# IIC_LCD.net
KiCad netlist of a schematic drawn in Altium Designer
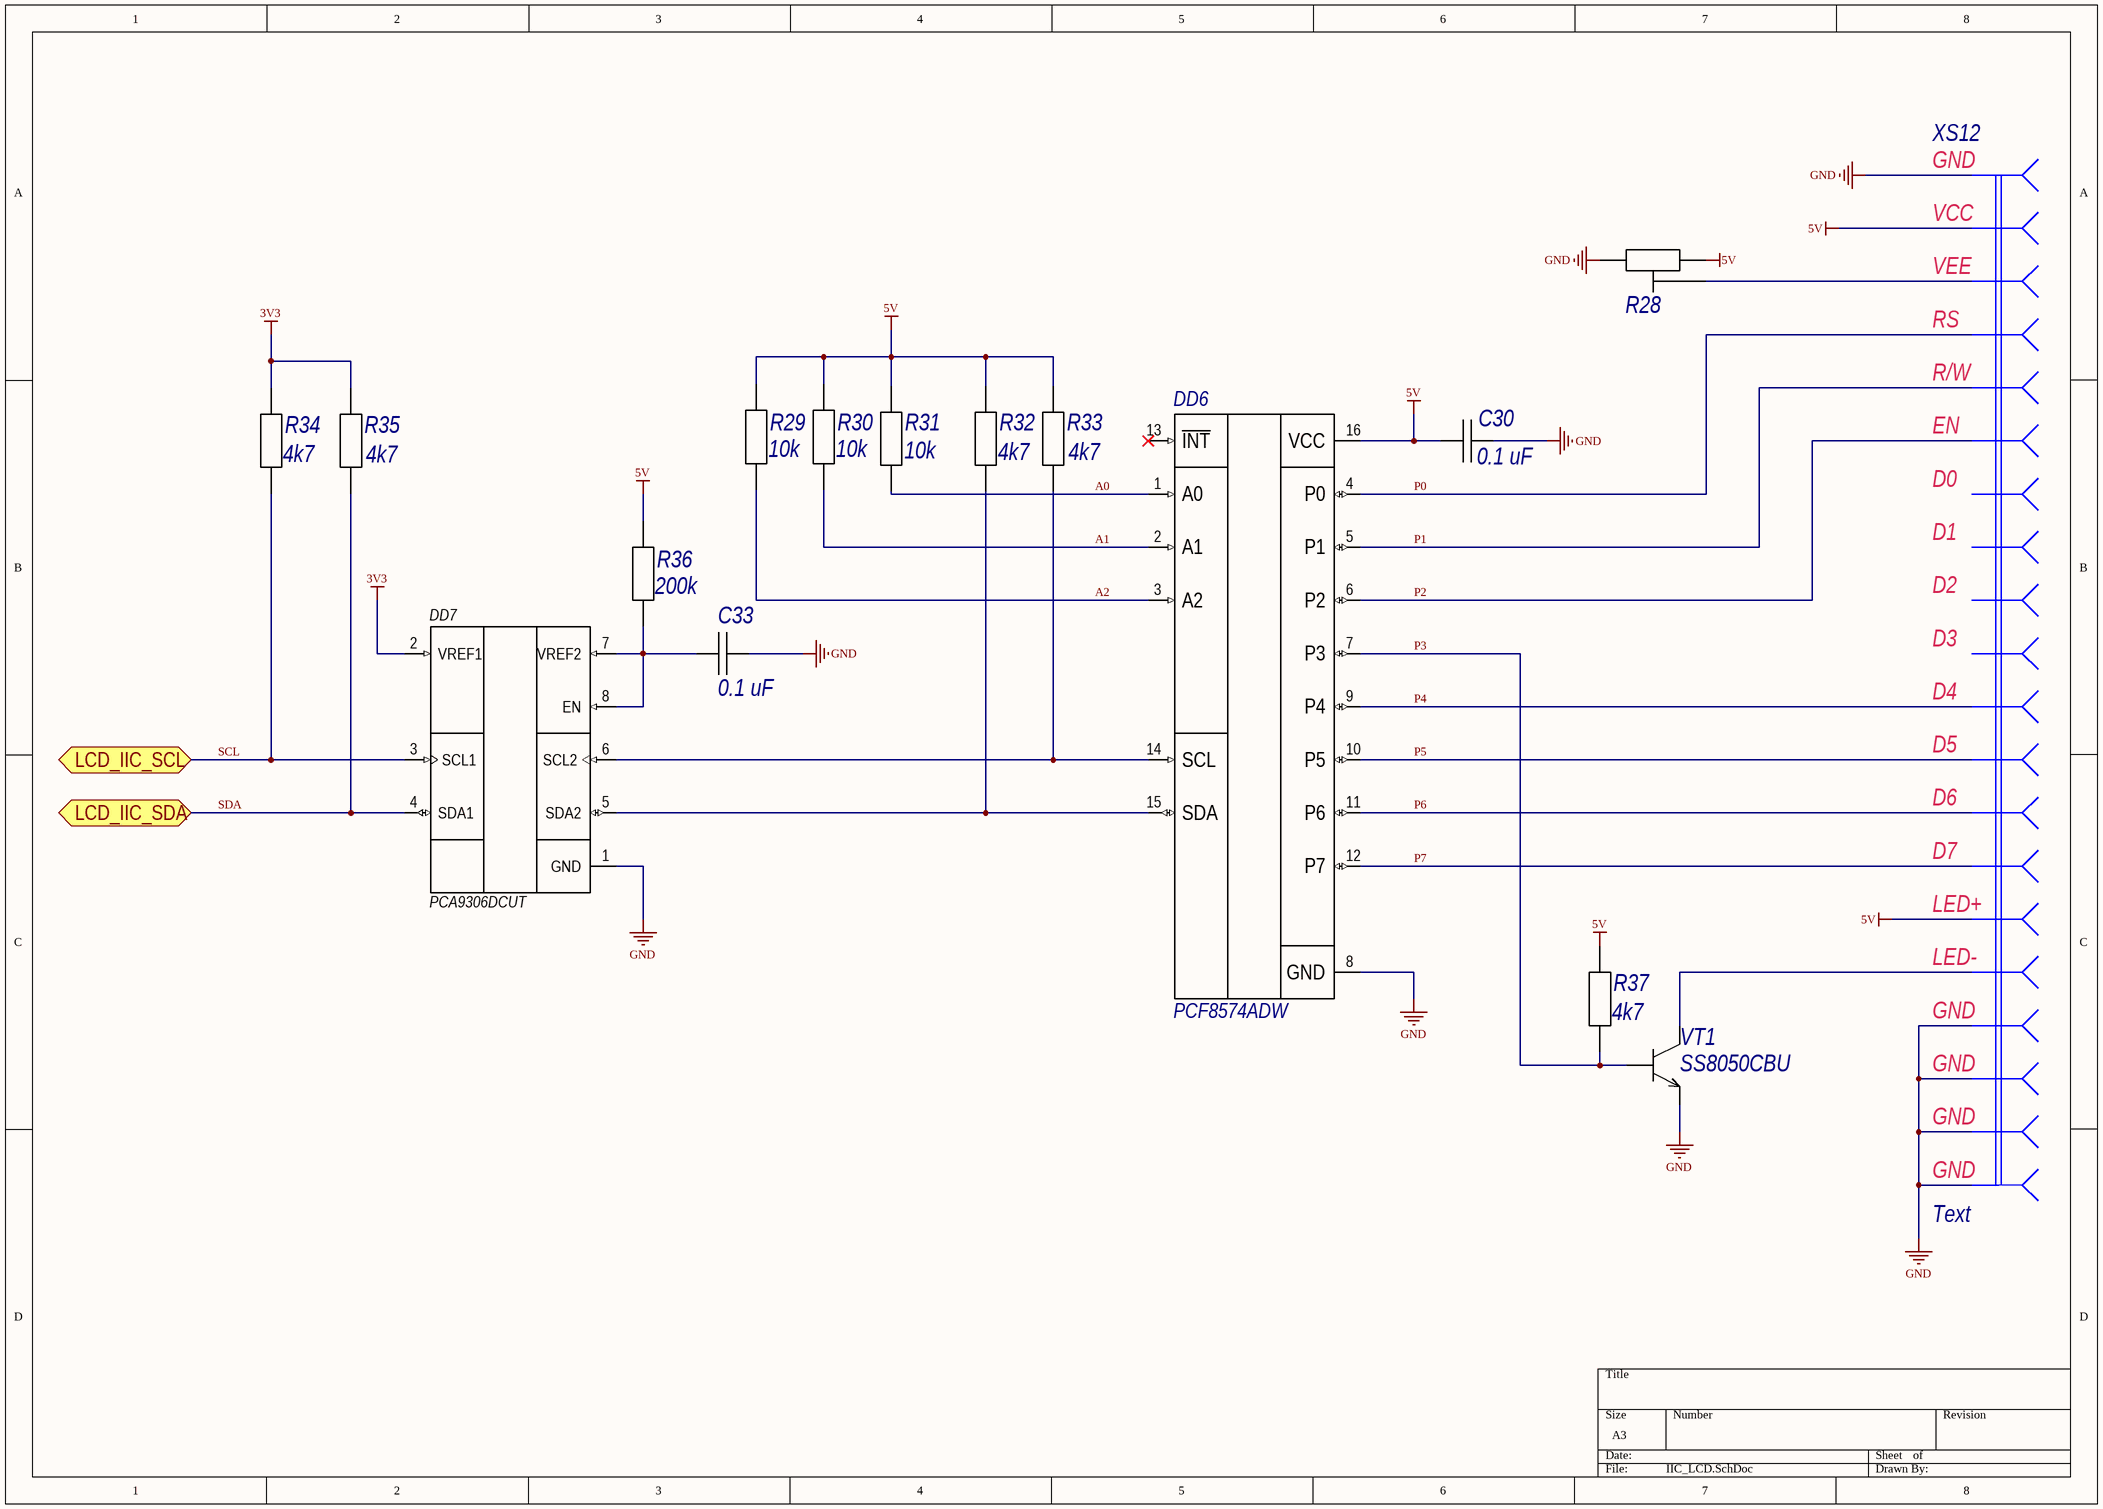
[diagram p0: IIC_LCD.SchDoc]

(export (version "E")
  (design (tool "Eeschema 10.0.6"))
  (components
    (comp (ref "C30")
      (value "0.1 uF")
      (footprint "C0805C")
      (fields (field (name "PUBLISHER") "Andrew Danich"))
      (libsource (lib "PA_control_board") (part "CAP_0805"))
    )
    (comp (ref "C33")
      (value "0.1 uF")
      (footprint "C0805C")
      (fields (field (name "PUBLISHER") "Andrew Danich"))
      (libsource (lib "PA_control_board") (part "CAP_0805"))
    )
    (comp (ref "DD6")
      (value "PCF8574ADW")
      (footprint "SOIC127P1030X265-16N")
      (description "Remote 8-Bit I/O Expander for I2C-Bus 16-SOIC -40 to 85")
      (fields (field (name "MF") "Texas Instruments"))
      (libsource (lib "PA_control_board") (part "PCF8574ADW"))
    )
    (comp (ref "DD7")
      (value "PCA9306DCUT")
      (footprint "SOP50P310X90-8N")
      (description "2-bit bidirectional I2C bus and SMBus voltage-level shifter 8-VSSOP -40 to 85")
      (fields (field (name "MF") "Texas Instruments"))
      (libsource (lib "PA_control_board") (part "PCA9306DCUT"))
    )
    (comp (ref "R28")
      (value "RES_VAR")
      (footprint "TRIM_3296W-1-254LF")
      (fields (field (name "PUBLISHER") "Andrew Danich"))
      (libsource (lib "PA_control_board") (part "RES_VAR"))
    )
    (comp (ref "R29")
      (value "10k")
      (footprint "C0805R")
      (fields (field (name "PUBLISHER") "Andrew Danich"))
      (libsource (lib "PA_control_board") (part "RES_0805"))
    )
    (comp (ref "R30")
      (value "10k")
      (footprint "C0805R")
      (fields (field (name "PUBLISHER") "Andrew Danich"))
      (libsource (lib "PA_control_board") (part "RES_0805"))
    )
    (comp (ref "R31")
      (value "10k")
      (footprint "C0805R")
      (fields (field (name "PUBLISHER") "Andrew Danich"))
      (libsource (lib "PA_control_board") (part "RES_0805"))
    )
    (comp (ref "R32")
      (value "4k7")
      (footprint "C0805R")
      (fields (field (name "PUBLISHER") "Andrew Danich"))
      (libsource (lib "PA_control_board") (part "RES_0805"))
    )
    (comp (ref "R33")
      (value "4k7")
      (footprint "C0805R")
      (fields (field (name "PUBLISHER") "Andrew Danich"))
      (libsource (lib "PA_control_board") (part "RES_0805"))
    )
    (comp (ref "R34")
      (value "4k7")
      (footprint "C0805R")
      (fields (field (name "PUBLISHER") "Andrew Danich"))
      (libsource (lib "PA_control_board") (part "RES_0805"))
    )
    (comp (ref "R35")
      (value "4k7")
      (footprint "C0805R")
      (fields (field (name "PUBLISHER") "Andrew Danich"))
      (libsource (lib "PA_control_board") (part "RES_0805"))
    )
    (comp (ref "R36")
      (value "200k")
      (footprint "C0805R")
      (fields (field (name "PUBLISHER") "Andrew Danich"))
      (libsource (lib "PA_control_board") (part "RES_0805"))
    )
    (comp (ref "R37")
      (value "4k7")
      (footprint "C0805R")
      (fields (field (name "PUBLISHER") "Andrew Danich"))
      (libsource (lib "PA_control_board") (part "RES_0805"))
    )
    (comp (ref "VT1")
      (value "SS8050CBU")
      (footprint "TO-92-A")
      (fields (field (name "PUBLISHER") "Andrew Danich"))
      (libsource (lib "PA_control_board") (part "SS8050CBU"))
    )
    (comp (ref "XS12")
      (value "Text")
      (footprint "IDC-20")
      (fields (field (name "PUBLISHER") "Andrew Danich"))
      (libsource (lib "PA_control_board") (part "CONNECT_LCD"))
    )
  )
  (nets
    (net (code "1") (name "/A0") (class "Default")
      (node (ref "DD6") (pin "1") (pinfunction "A0_1") (pintype "input"))
      (node (ref "R31") (pin "1") (pinfunction "1_1") (pintype "passive"))
    )
    (net (code "2") (name "/A1") (class "Default")
      (node (ref "DD6") (pin "2") (pinfunction "A1_2") (pintype "input"))
      (node (ref "R30") (pin "1") (pinfunction "1_1") (pintype "passive"))
    )
    (net (code "3") (name "/A2") (class "Default")
      (node (ref "DD6") (pin "3") (pinfunction "A2_3") (pintype "input"))
      (node (ref "R29") (pin "1") (pinfunction "1_1") (pintype "passive"))
    )
    (net (code "4") (name "/P0") (class "Default")
      (node (ref "DD6") (pin "4") (pinfunction "P0_4") (pintype "bidirectional"))
      (node (ref "XS12") (pin "4") (pintype "passive"))
    )
    (net (code "5") (name "/P1") (class "Default")
      (node (ref "DD6") (pin "5") (pinfunction "P1_5") (pintype "bidirectional"))
      (node (ref "XS12") (pin "5") (pintype "passive"))
    )
    (net (code "6") (name "/P2") (class "Default")
      (node (ref "DD6") (pin "6") (pinfunction "P2_6") (pintype "bidirectional"))
      (node (ref "XS12") (pin "6") (pintype "passive"))
    )
    (net (code "7") (name "/P3") (class "Default")
      (node (ref "DD6") (pin "7") (pinfunction "P3_7") (pintype "bidirectional"))
      (node (ref "R37") (pin "1") (pinfunction "1_1") (pintype "passive"))
      (node (ref "VT1") (pin "1") (pinfunction "Б_1") (pintype "passive"))
    )
    (net (code "8") (name "/P4") (class "Default")
      (node (ref "DD6") (pin "9") (pinfunction "P4_9") (pintype "bidirectional"))
      (node (ref "XS12") (pin "11") (pintype "passive"))
    )
    (net (code "9") (name "/P5") (class "Default")
      (node (ref "DD6") (pin "10") (pinfunction "P5_10") (pintype "bidirectional"))
      (node (ref "XS12") (pin "12") (pintype "passive"))
    )
    (net (code "10") (name "/P6") (class "Default")
      (node (ref "DD6") (pin "11") (pinfunction "P6_11") (pintype "bidirectional"))
      (node (ref "XS12") (pin "13") (pintype "passive"))
    )
    (net (code "11") (name "/P7") (class "Default")
      (node (ref "DD6") (pin "12") (pinfunction "P7_12") (pintype "bidirectional"))
      (node (ref "XS12") (pin "14") (pintype "passive"))
    )
    (net (code "12") (name "/SCL") (class "Default")
      (node (ref "DD7") (pin "3") (pinfunction "SCL1_3") (pintype "input"))
      (node (ref "R34") (pin "1") (pinfunction "1_1") (pintype "passive"))
    )
    (net (code "13") (name "/SDA") (class "Default")
      (node (ref "DD7") (pin "4") (pinfunction "SDA1_4") (pintype "bidirectional"))
      (node (ref "R35") (pin "1") (pinfunction "1_1") (pintype "passive"))
    )
    (net (code "14") (name "3V3") (class "Default")
      (node (ref "DD7") (pin "2") (pinfunction "VREF1_2") (pintype "input"))
      (node (ref "R34") (pin "2") (pinfunction "2_2") (pintype "passive"))
      (node (ref "R35") (pin "2") (pinfunction "2_2") (pintype "passive"))
    )
    (net (code "15") (name "5V") (class "Default")
      (node (ref "C30") (pin "2") (pinfunction "2_2") (pintype "passive"))
      (node (ref "DD6") (pin "16") (pinfunction "VCC_16") (pintype "power_in"))
      (node (ref "R28") (pin "1") (pinfunction "1_1") (pintype "passive"))
      (node (ref "R29") (pin "2") (pinfunction "2_2") (pintype "passive"))
      (node (ref "R30") (pin "2") (pinfunction "2_2") (pintype "passive"))
      (node (ref "R31") (pin "2") (pinfunction "2_2") (pintype "passive"))
      (node (ref "R32") (pin "2") (pinfunction "2_2") (pintype "passive"))
      (node (ref "R33") (pin "2") (pinfunction "2_2") (pintype "passive"))
      (node (ref "R36") (pin "2") (pinfunction "2_2") (pintype "passive"))
      (node (ref "R37") (pin "2") (pinfunction "2_2") (pintype "passive"))
      (node (ref "XS12") (pin "15") (pintype "passive"))
      (node (ref "XS12") (pin "2") (pintype "passive"))
    )
    (net (code "16") (name "GND") (class "Default")
      (node (ref "C30") (pin "1") (pinfunction "1_1") (pintype "passive"))
      (node (ref "C33") (pin "2") (pinfunction "2_2") (pintype "passive"))
      (node (ref "DD6") (pin "8") (pinfunction "GND_8") (pintype "power_in"))
      (node (ref "DD7") (pin "1") (pinfunction "GND_1") (pintype "power_in"))
      (node (ref "R28") (pin "3") (pinfunction "3_3") (pintype "passive"))
      (node (ref "VT1") (pin "3") (pinfunction "Э_3") (pintype "passive"))
      (node (ref "XS12") (pin "1") (pintype "passive"))
      (node (ref "XS12") (pin "17") (pintype "passive"))
      (node (ref "XS12") (pin "18") (pintype "passive"))
      (node (ref "XS12") (pin "19") (pintype "passive"))
      (node (ref "XS12") (pin "20") (pintype "passive"))
    )
    (net (code "17") (name "Net-(DD6-SCL)") (class "Default")
      (node (ref "DD6") (pin "14") (pinfunction "SCL_14") (pintype "input"))
      (node (ref "DD7") (pin "6") (pinfunction "SCL2_6") (pintype "input"))
      (node (ref "R33") (pin "1") (pinfunction "1_1") (pintype "passive"))
    )
    (net (code "18") (name "Net-(DD6-SDA)") (class "Default")
      (node (ref "DD6") (pin "15") (pinfunction "SDA_15") (pintype "bidirectional"))
      (node (ref "DD7") (pin "5") (pinfunction "SDA2_5") (pintype "bidirectional"))
      (node (ref "R32") (pin "1") (pinfunction "1_1") (pintype "passive"))
    )
    (net (code "19") (name "Net-(DD7-EN)") (class "Default")
      (node (ref "C33") (pin "1") (pinfunction "1_1") (pintype "passive"))
      (node (ref "DD7") (pin "7") (pinfunction "VREF2_7") (pintype "input"))
      (node (ref "DD7") (pin "8") (pinfunction "EN_8") (pintype "input"))
      (node (ref "R36") (pin "1") (pinfunction "1_1") (pintype "passive"))
    )
    (net (code "20") (name "Net-(R28-Pad2)") (class "Default")
      (node (ref "R28") (pin "2") (pinfunction "2_2") (pintype "passive"))
      (node (ref "XS12") (pin "3") (pintype "passive"))
    )
    (net (code "21") (name "Net-(VT1-К)") (class "Default")
      (node (ref "VT1") (pin "2") (pinfunction "К_2") (pintype "passive"))
      (node (ref "XS12") (pin "16") (pintype "passive"))
    )
    (net (code "22") (name "unconnected-(DD6-~{INT}-Pad13)") (class "Default")
      (node (ref "DD6") (pin "13") (pinfunction "~{INT}_13") (pintype "input+no_connect"))
    )
    (net (code "23") (name "unconnected-(XS12-Pad7)") (class "Default")
      (node (ref "XS12") (pin "7") (pintype "passive"))
    )
    (net (code "24") (name "unconnected-(XS12-Pad8)") (class "Default")
      (node (ref "XS12") (pin "8") (pintype "passive"))
    )
    (net (code "25") (name "unconnected-(XS12-Pad9)") (class "Default")
      (node (ref "XS12") (pin "9") (pintype "passive"))
    )
    (net (code "26") (name "unconnected-(XS12-Pad10)") (class "Default")
      (node (ref "XS12") (pin "10") (pintype "passive"))
    )
  )
)
